# main.net
KiCad netlist of a schematic drawn in Altium Designer
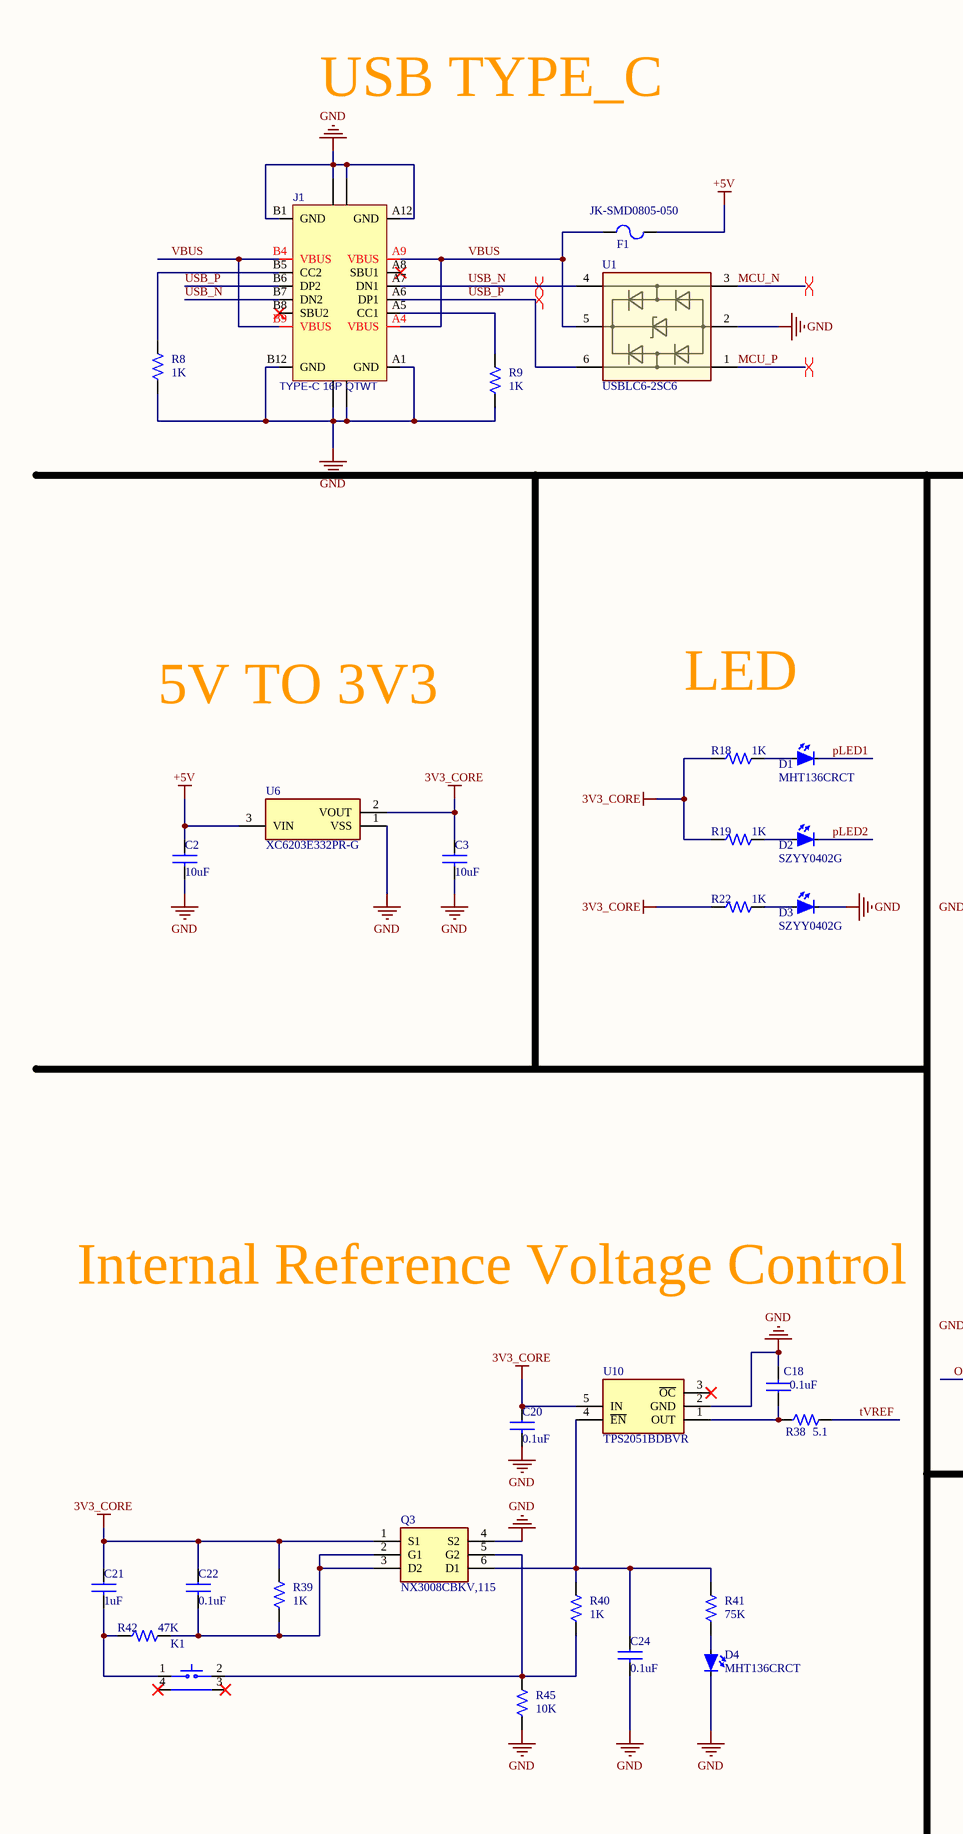
[diagram p0: main.SchDoc, left]
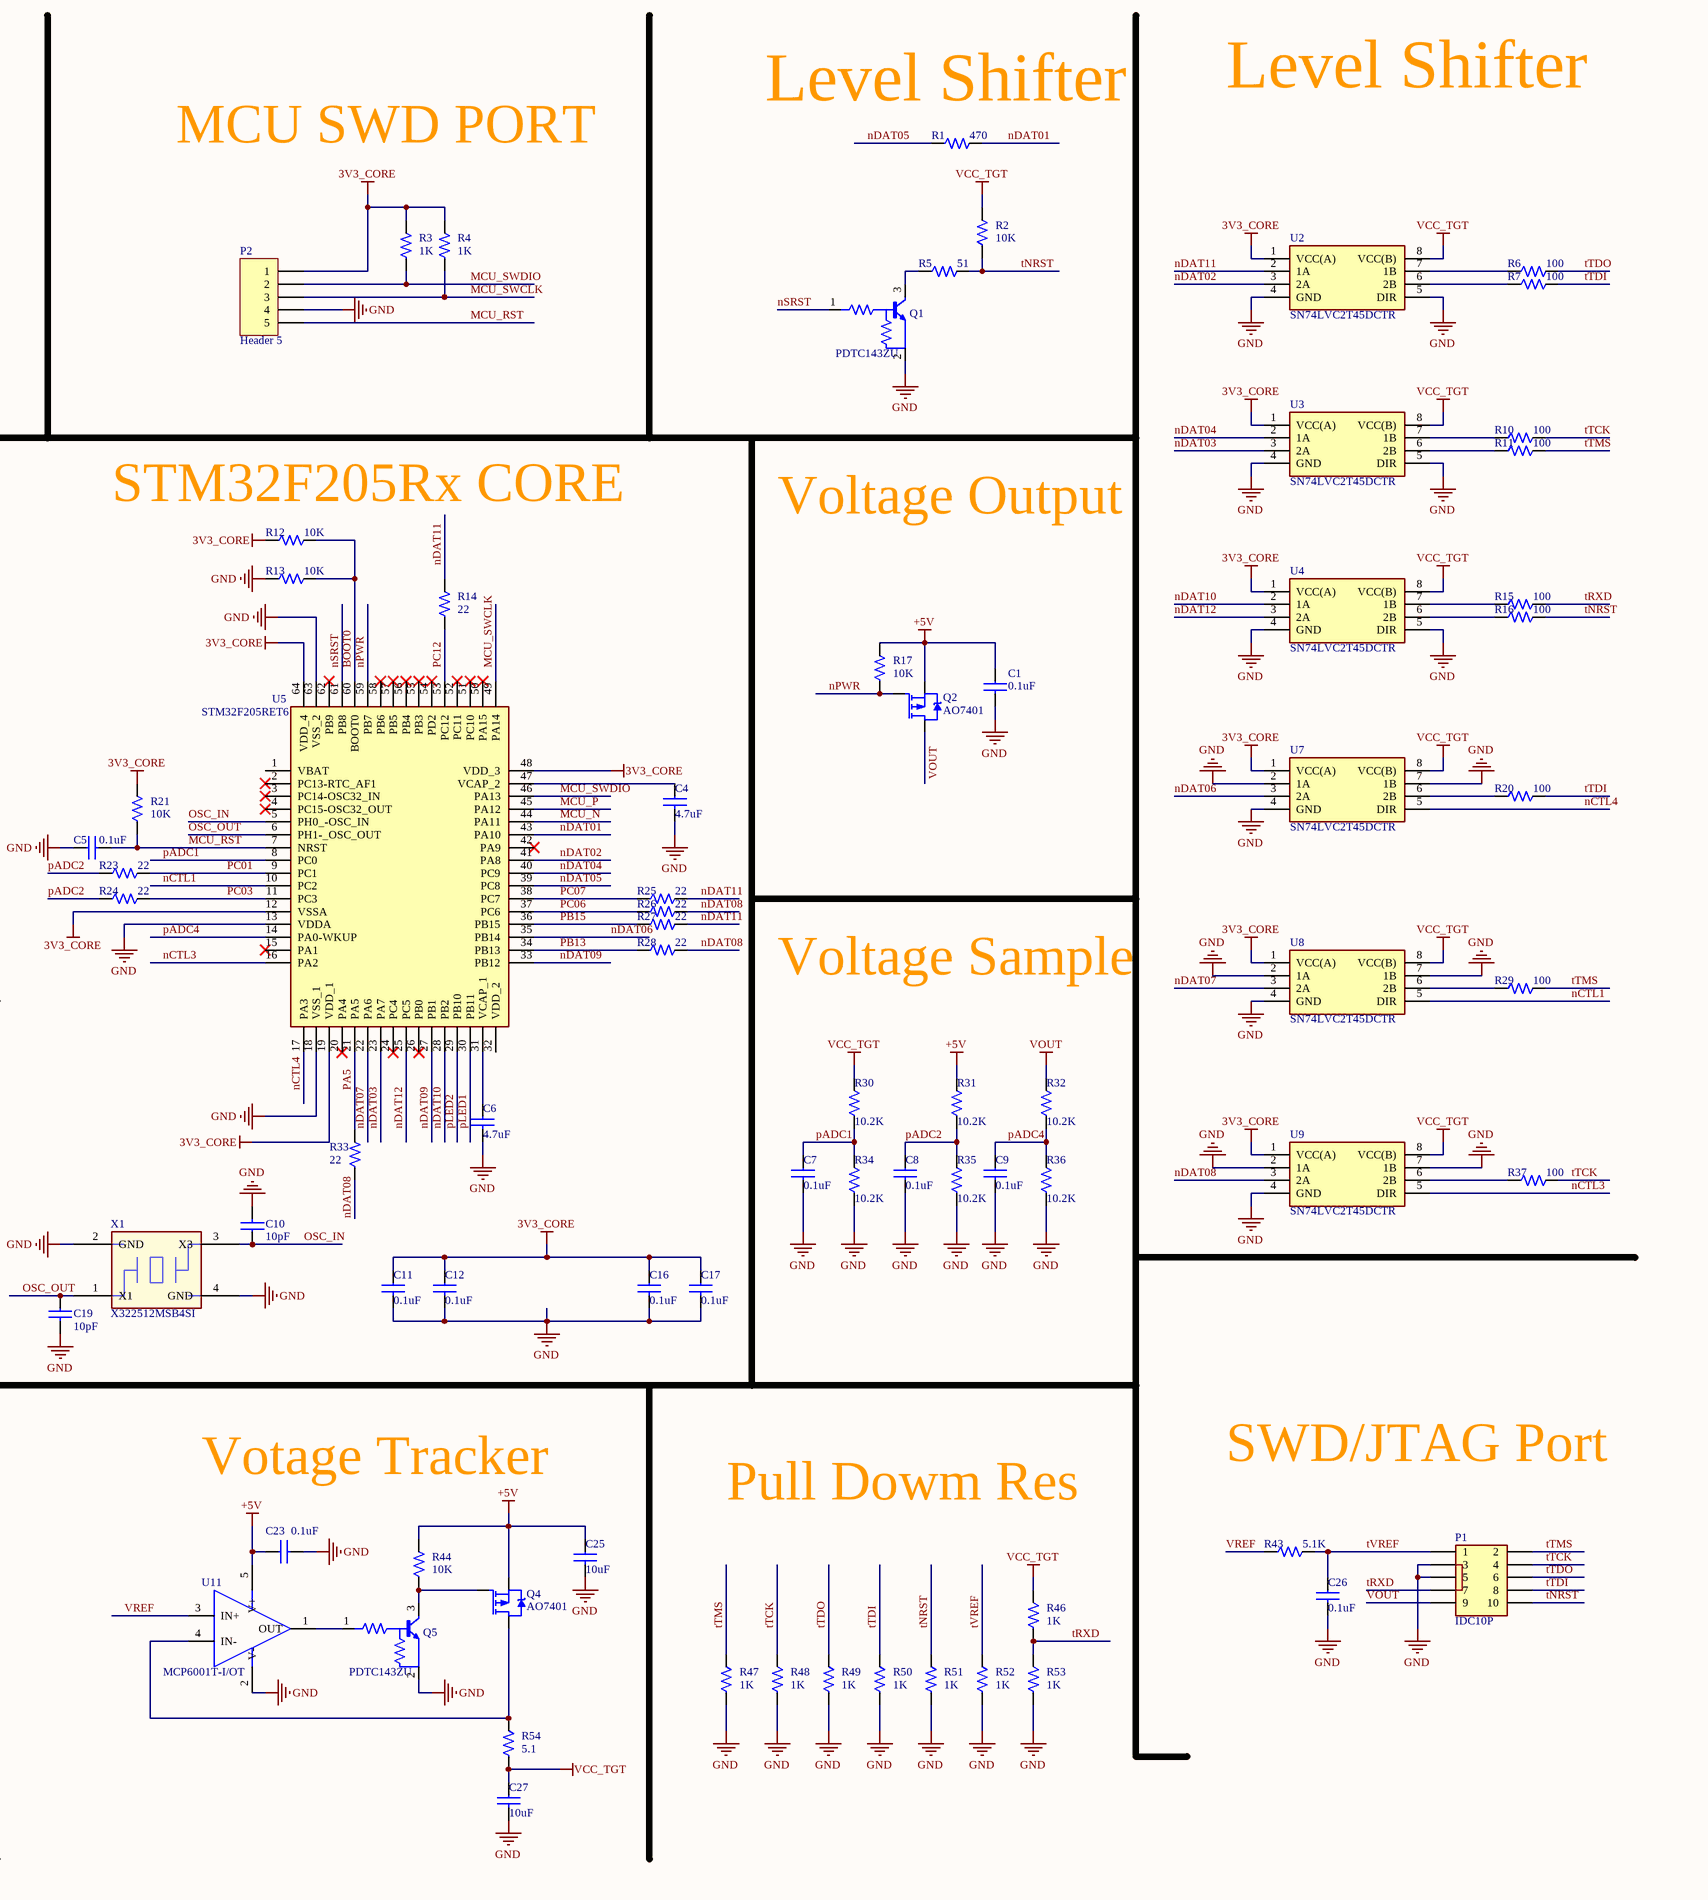
[diagram p1: main.SchDoc, right]

(export (version "E")
  (design (tool "Eeschema 10.0.6"))
  (components
    (comp (ref "C1")
      (value "0.1uF")
      (footprint "C0402")
      (description "CAP CER 0.1uF 25V X7R 0402")
      (fields (field (name "PART NUMBER") "E01C01711") (field (name "POWER") "25V"))
      (libsource (lib "Library") (part "CAP NON POL"))
    )
    (comp (ref "C2")
      (value "10uF")
      (footprint "C0402")
      (description "CAP CER 10uF 6.3V X5R 0402")
      (fields (field (name "PART NUMBER") "E01C02000") (field (name "POWER") "6.3V"))
      (libsource (lib "Library") (part "CAP NON POL"))
    )
    (comp (ref "C3")
      (value "10uF")
      (footprint "C0402")
      (description "CAP CER 10uF 6.3V X5R 0402")
      (fields (field (name "PART NUMBER") "E01C02000") (field (name "POWER") "6.3V"))
      (libsource (lib "Library") (part "CAP NON POL"))
    )
    (comp (ref "C4")
      (value "4.7uF")
      (footprint "C0402")
      (description "CAP CER 4.7uF 10V X5R 0402")
      (fields (field (name "PART NUMBER") "E01C01942") (field (name "POWER") "10V"))
      (libsource (lib "Library") (part "CAP NON POL"))
    )
    (comp (ref "C5")
      (value "0.1uF")
      (footprint "C0402")
      (description "CAP CER 0.1uF 25V X7R 0402")
      (fields (field (name "PART NUMBER") "E01C01711") (field (name "POWER") "25V"))
      (libsource (lib "Library") (part "CAP NON POL"))
    )
    (comp (ref "C6")
      (value "4.7uF")
      (footprint "C0402")
      (description "CAP CER 4.7uF 10V X5R 0402")
      (fields (field (name "PART NUMBER") "E01C01942") (field (name "POWER") "10V"))
      (libsource (lib "Library") (part "CAP NON POL"))
    )
    (comp (ref "C7")
      (value "0.1uF")
      (footprint "C0402")
      (description "CAP CER 0.1uF 16V X7R 0402")
      (fields (field (name "PART NUMBER") "E01C01713") (field (name "POWER") "16V"))
      (libsource (lib "Library") (part "CAP NON POL"))
    )
    (comp (ref "C8")
      (value "0.1uF")
      (footprint "C0402")
      (description "CAP CER 0.1uF 16V X7R 0402")
      (fields (field (name "PART NUMBER") "E01C01713") (field (name "POWER") "16V"))
      (libsource (lib "Library") (part "CAP NON POL"))
    )
    (comp (ref "C9")
      (value "0.1uF")
      (footprint "C0402")
      (description "CAP CER 0.1uF 16V X7R 0402")
      (fields (field (name "PART NUMBER") "E01C01713") (field (name "POWER") "16V"))
      (libsource (lib "Library") (part "CAP NON POL"))
    )
    (comp (ref "C10")
      (value "10pF")
      (footprint "C0402")
      (description "CAP CER 10pF 50V C0G/NP0 0402")
      (fields (field (name "PART NUMBER") "E01C00842") (field (name "POWER") "50V"))
      (libsource (lib "Library") (part "CAP NON POL"))
    )
    (comp (ref "C11")
      (value "0.1uF")
      (footprint "C0402")
      (description "CAP CER 0.1uF 16V X7R 0402")
      (fields (field (name "PART NUMBER") "E01C01713") (field (name "POWER") "16V"))
      (libsource (lib "Library") (part "CAP NON POL"))
    )
    (comp (ref "C12")
      (value "0.1uF")
      (footprint "C0402")
      (description "CAP CER 0.1uF 16V X7R 0402")
      (fields (field (name "PART NUMBER") "E01C01713") (field (name "POWER") "16V"))
      (libsource (lib "Library") (part "CAP NON POL"))
    )
    (comp (ref "C16")
      (value "0.1uF")
      (footprint "C0402")
      (description "CAP CER 0.1uF 16V X7R 0402")
      (fields (field (name "PART NUMBER") "E01C01713") (field (name "POWER") "16V"))
      (libsource (lib "Library") (part "CAP NON POL"))
    )
    (comp (ref "C17")
      (value "0.1uF")
      (footprint "C0402")
      (description "CAP CER 0.1uF 16V X7R 0402")
      (fields (field (name "PART NUMBER") "E01C01713") (field (name "POWER") "16V"))
      (libsource (lib "Library") (part "CAP NON POL"))
    )
    (comp (ref "C18")
      (value "0.1uF")
      (footprint "C0402")
      (description "CAP CER 0.1uF 25V X7R 0402")
      (fields (field (name "PART NUMBER") "E01C01711") (field (name "POWER") "25V"))
      (libsource (lib "Library") (part "CAP NON POL"))
    )
    (comp (ref "C19")
      (value "10pF")
      (footprint "C0402")
      (description "CAP CER 10pF 50V C0G/NP0 0402")
      (fields (field (name "PART NUMBER") "E01C00842") (field (name "POWER") "50V"))
      (libsource (lib "Library") (part "CAP NON POL"))
    )
    (comp (ref "C20")
      (value "0.1uF")
      (footprint "C0402")
      (description "CAP CER 0.1uF 25V X7R 0402")
      (fields (field (name "PART NUMBER") "E01C01711") (field (name "POWER") "25V"))
      (libsource (lib "Library") (part "CAP NON POL"))
    )
    (comp (ref "C21")
      (value "1uF")
      (footprint "C0402")
      (description "CAP CER 1uF 6.3V X5R 0402")
      (fields (field (name "PART NUMBER") "E01C01812") (field (name "POWER") "6.3V"))
      (libsource (lib "Library") (part "CAP NON POL"))
    )
    (comp (ref "C22")
      (value "0.1uF")
      (footprint "C0402")
      (description "CAP CER 0.1uF 25V X7R 0402")
      (fields (field (name "PART NUMBER") "E01C01711") (field (name "POWER") "25V"))
      (libsource (lib "Library") (part "CAP NON POL"))
    )
    (comp (ref "C23")
      (value "0.1uF")
      (footprint "C0402")
      (description "CAP CER 0.1uF 16V X7R 0402")
      (fields (field (name "PART NUMBER") "E01C01713") (field (name "POWER") "16V"))
      (libsource (lib "Library") (part "CAP NON POL"))
    )
    (comp (ref "C24")
      (value "0.1uF")
      (footprint "C0402")
      (description "CAP CER 0.1uF 25V X7R 0402")
      (fields (field (name "PART NUMBER") "E01C01711") (field (name "POWER") "25V"))
      (libsource (lib "Library") (part "CAP NON POL"))
    )
    (comp (ref "C25")
      (value "10uF")
      (footprint "C0402")
      (description "CAP CER 10uF 6.3V X5R 0402")
      (fields (field (name "PART NUMBER") "E01C02000") (field (name "POWER") "6.3V"))
      (libsource (lib "Library") (part "CAP NON POL"))
    )
    (comp (ref "C26")
      (value "0.1uF")
      (footprint "C0402")
      (description "CAP CER 0.1uF 25V X7R 0402")
      (fields (field (name "PART NUMBER") "E01C01711") (field (name "POWER") "25V"))
      (libsource (lib "Library") (part "CAP NON POL"))
    )
    (comp (ref "C27")
      (value "10uF")
      (footprint "C0603")
      (description "CAP CER 10uF 16V X5R 0603")
      (fields (field (name "PART NUMBER") "E01C01977") (field (name "POWER") "16V"))
      (libsource (lib "Library") (part "CAP NON POL"))
    )
    (comp (ref "D1")
      (value "MHT136CRCT")
      (footprint "LED-0402")
      (description "SMD,发光颜色:红色;功率:60mW;正向电流:5mA;主波长:617.5nm~633.5nm;")
      (fields (field (name "PART NUMBER") "E01D00051") (field (name "MFG") "MEIHUA"))
      (libsource (lib "Library") (part "LED"))
    )
    (comp (ref "D2")
      (value "SZYY0402G")
      (footprint "LED-0402")
      (description "SMD,发光颜色:翠绿色;")
      (fields (field (name "PART NUMBER") "E01D00010") (field (name "MFG") "YONGYU"))
      (libsource (lib "Library") (part "LED"))
    )
    (comp (ref "D3")
      (value "SZYY0402G")
      (footprint "LED-0402")
      (description "SMD,发光颜色:翠绿色;")
      (fields (field (name "PART NUMBER") "E01D00010") (field (name "MFG") "YONGYU"))
      (libsource (lib "Library") (part "LED"))
    )
    (comp (ref "D4")
      (value "MHT136CRCT")
      (footprint "LED-0402")
      (description "SMD,发光颜色:红色;功率:60mW;正向电流:5mA;主波长:617.5nm~633.5nm;")
      (fields (field (name "PART NUMBER") "E01D00051") (field (name "MFG") "MEIHUA"))
      (libsource (lib "Library") (part "LED"))
    )
    (comp (ref "F1")
      (value "JK-SMD0805-050")
      (footprint "FUSE_0805")
      (description "0805 0.5A 6V PTC FUSE")
      (fields (field (name "PART NUMBER") "E01F00003") (field (name "POWER") "6V"))
      (libsource (lib "Library") (part "FUSE"))
    )
    (comp (ref "J1")
      (value "TYPE-C 16P QTWT")
      (footprint "USB-C-16-SM")
      (description "SMD,Type_C母座；16P；卧贴;")
      (fields (field (name "PART NUMBER") "E04C00183") (field (name "MFG") "SHOU HAN"))
      (libsource (lib "Library") (part "USB2.0_Type-C_16Pin"))
    )
    (comp (ref "K1")
      (value "TS36CA-0.6")
      (footprint "SW4-3X6X3R5-WS")
      (description "SMD,轻触开关 3*6*3.5侧按 直径0.6定位柱 白体黑头")
      (fields (field (name "PART NUMBER") "E01S00008") (field (name "MFG") "SHOU HAN(首韩)"))
      (libsource (lib "Library") (part "SW-4Pin_1"))
    )
    (comp (ref "P1")
      (value "IDC10P")
      (footprint "IDC10P-2R54-WS")
      (description "SMD.2.54mm简牛座;卧贴;排数:2;每排PIN数:5")
      (fields (field (name "PART NUMBER") "E04C00186") (field (name "MFG") "/"))
      (libsource (lib "Library") (part "CON2x5"))
    )
    (comp (ref "P2")
      (value "Device Name")
      (footprint "HDR-1.27-1X5")
      (description "5脚排针")
      (fields (field (name "SCH NAME") "Header 5") (field (name "PART NUMBER") "E04C00187"))
      (libsource (lib "Library") (part "Header 5"))
    )
    (comp (ref "Q1")
      (value "PDTC143ZU")
      (footprint "SOT323")
      (fields (field (name "PART NUMBER") "E01T00045") (field (name "MFG") "Nexperia"))
      (libsource (lib "Library") (part "Transistor Digital NPN"))
    )
    (comp (ref "Q2")
      (value "AO7401")
      (footprint "SOT23-3")
      (fields (field (name "PART NUMBER") "E01T00044") (field (name "MFG") "AOS"))
      (libsource (lib "Library") (part "PMOS"))
    )
    (comp (ref "Q3")
      (value "NX3008CBKV,115")
      (footprint "SOT666")
      (fields (field (name "PART NUMBER") "E01T00046") (field (name "MFG") "Nexperia"))
      (libsource (lib "Library") (part "PMOS_NMOS_6"))
    )
    (comp (ref "Q4")
      (value "AO7401")
      (footprint "SOT23-3")
      (fields (field (name "PART NUMBER") "E01T00044") (field (name "MFG") "AOS"))
      (libsource (lib "Library") (part "PMOS"))
    )
    (comp (ref "Q5")
      (value "PDTC143ZU")
      (footprint "SOT323")
      (fields (field (name "PART NUMBER") "E01T00045") (field (name "MFG") "Nexperia"))
      (libsource (lib "Library") (part "Transistor Digital NPN"))
    )
    (comp (ref "R1")
      (value "470")
      (footprint "R0402")
      (description "RES SMD 470 OHM 5% 1/16W 0402")
      (fields (field (name "PART NUMBER") "E01R01244") (field (name "POWER") "0.063W，1/16W"))
      (libsource (lib "Library") (part "RES"))
    )
    (comp (ref "R2")
      (value "10K")
      (footprint "R0402")
      (description "RES SMD 10K OHM 1% 1/16W 0402")
      (fields (field (name "PART NUMBER") "E01R01984") (field (name "POWER") "0.063W，1/16W"))
      (libsource (lib "Library") (part "RES"))
    )
    (comp (ref "R3")
      (value "1K")
      (footprint "R0402")
      (description "RES SMD 1K OHM 1% 1/16W 0402")
      (fields (field (name "PART NUMBER") "E01R01430") (field (name "POWER") "0.063W，1/16W"))
      (libsource (lib "Library") (part "RES"))
    )
    (comp (ref "R4")
      (value "1K")
      (footprint "R0402")
      (description "RES SMD 1K OHM 1% 1/16W 0402")
      (fields (field (name "PART NUMBER") "E01R01430") (field (name "POWER") "0.063W，1/16W"))
      (libsource (lib "Library") (part "RES"))
    )
    (comp (ref "R5")
      (value "51")
      (footprint "R0402")
      (description "RES SMD 51 OHM 1% 1/16W 0402")
      (fields (field (name "PART NUMBER") "E01R00720") (field (name "POWER") "0.063W，1/16W"))
      (libsource (lib "Library") (part "RES"))
    )
    (comp (ref "R6")
      (value "100")
      (footprint "R0402")
      (description "RES SMD 100 OHM 5% 1/16W 0402")
      (fields (field (name "PART NUMBER") "E01R00875") (field (name "POWER") "0.063W，1/16W"))
      (libsource (lib "Library") (part "RES"))
    )
    (comp (ref "R7")
      (value "100")
      (footprint "R0402")
      (description "RES SMD 100 OHM 5% 1/16W 0402")
      (fields (field (name "PART NUMBER") "E01R00875") (field (name "POWER") "0.063W，1/16W"))
      (libsource (lib "Library") (part "RES"))
    )
    (comp (ref "R8")
      (value "1K")
      (footprint "R0402")
      (description "RES SMD 1K OHM 1% 1/16W 0402")
      (fields (field (name "PART NUMBER") "E01R01430") (field (name "POWER") "0.063W，1/16W"))
      (libsource (lib "Library") (part "RES"))
    )
    (comp (ref "R9")
      (value "1K")
      (footprint "R0402")
      (description "RES SMD 1K OHM 1% 1/16W 0402")
      (fields (field (name "PART NUMBER") "E01R01430") (field (name "POWER") "0.063W，1/16W"))
      (libsource (lib "Library") (part "RES"))
    )
    (comp (ref "R10")
      (value "100")
      (footprint "R0402")
      (description "RES SMD 100 OHM 5% 1/16W 0402")
      (fields (field (name "PART NUMBER") "E01R00875") (field (name "POWER") "0.063W，1/16W"))
      (libsource (lib "Library") (part "RES"))
    )
    (comp (ref "R11")
      (value "100")
      (footprint "R0402")
      (description "RES SMD 100 OHM 5% 1/16W 0402")
      (fields (field (name "PART NUMBER") "E01R00875") (field (name "POWER") "0.063W，1/16W"))
      (libsource (lib "Library") (part "RES"))
    )
    (comp (ref "R12")
      (value "10K")
      (footprint "R0402")
      (description "RES SMD 10K OHM 1% 1/16W 0402")
      (fields (field (name "PART NUMBER") "E01R01984") (field (name "POWER") "0.063W，1/16W"))
      (libsource (lib "Library") (part "RES"))
    )
    (comp (ref "R13")
      (value "10K")
      (footprint "R0402")
      (description "RES SMD 10K OHM 1% 1/16W 0402")
      (fields (field (name "PART NUMBER") "E01R01984") (field (name "POWER") "0.063W，1/16W"))
      (libsource (lib "Library") (part "RES"))
    )
    (comp (ref "R14")
      (value "22")
      (footprint "R0402")
      (description "RES SMD 22 OHM 1% 1/16W 0402")
      (fields (field (name "PART NUMBER") "E01R00510") (field (name "POWER") "0.063W，1/16W"))
      (libsource (lib "Library") (part "RES"))
    )
    (comp (ref "R15")
      (value "100")
      (footprint "R0402")
      (description "RES SMD 100 OHM 5% 1/16W 0402")
      (fields (field (name "PART NUMBER") "E01R00875") (field (name "POWER") "0.063W，1/16W"))
      (libsource (lib "Library") (part "RES"))
    )
    (comp (ref "R16")
      (value "100")
      (footprint "R0402")
      (description "RES SMD 100 OHM 5% 1/16W 0402")
      (fields (field (name "PART NUMBER") "E01R00875") (field (name "POWER") "0.063W，1/16W"))
      (libsource (lib "Library") (part "RES"))
    )
    (comp (ref "R17")
      (value "10K")
      (footprint "R0402")
      (description "RES SMD 10K OHM 1% 1/16W 0402")
      (fields (field (name "PART NUMBER") "E01R01984") (field (name "POWER") "0.063W，1/16W"))
      (libsource (lib "Library") (part "RES"))
    )
    (comp (ref "R18")
      (value "1K")
      (footprint "R0402")
      (description "RES SMD 1K OHM 1% 1/16W 0402")
      (fields (field (name "PART NUMBER") "E01R01430") (field (name "POWER") "0.063W，1/16W"))
      (libsource (lib "Library") (part "RES"))
    )
    (comp (ref "R19")
      (value "1K")
      (footprint "R0402")
      (description "RES SMD 1K OHM 1% 1/16W 0402")
      (fields (field (name "PART NUMBER") "E01R01430") (field (name "POWER") "0.063W，1/16W"))
      (libsource (lib "Library") (part "RES"))
    )
    (comp (ref "R20")
      (value "100")
      (footprint "R0402")
      (description "RES SMD 100 OHM 5% 1/16W 0402")
      (fields (field (name "PART NUMBER") "E01R00875") (field (name "POWER") "0.063W，1/16W"))
      (libsource (lib "Library") (part "RES"))
    )
    (comp (ref "R21")
      (value "10K")
      (footprint "R0402")
      (description "RES SMD 10K OHM 1% 1/16W 0402")
      (fields (field (name "PART NUMBER") "E01R01984") (field (name "POWER") "0.063W，1/16W"))
      (libsource (lib "Library") (part "RES"))
    )
    (comp (ref "R22")
      (value "1K")
      (footprint "R0402")
      (description "RES SMD 1K OHM 1% 1/16W 0402")
      (fields (field (name "PART NUMBER") "E01R01430") (field (name "POWER") "0.063W，1/16W"))
      (libsource (lib "Library") (part "RES"))
    )
    (comp (ref "R23")
      (value "22")
      (footprint "R0402")
      (description "RES SMD 22 OHM 1% 1/16W 0402")
      (fields (field (name "PART NUMBER") "E01R00510") (field (name "POWER") "0.063W，1/16W"))
      (libsource (lib "Library") (part "RES"))
    )
    (comp (ref "R24")
      (value "22")
      (footprint "R0402")
      (description "RES SMD 22 OHM 1% 1/16W 0402")
      (fields (field (name "PART NUMBER") "E01R00510") (field (name "POWER") "0.063W，1/16W"))
      (libsource (lib "Library") (part "RES"))
    )
    (comp (ref "R25")
      (value "22")
      (footprint "R0402")
      (description "RES SMD 22 OHM 1% 1/16W 0402")
      (fields (field (name "PART NUMBER") "E01R00510") (field (name "POWER") "0.063W，1/16W"))
      (libsource (lib "Library") (part "RES"))
    )
    (comp (ref "R26")
      (value "22")
      (footprint "R0402")
      (description "RES SMD 22 OHM 1% 1/16W 0402")
      (fields (field (name "PART NUMBER") "E01R00510") (field (name "POWER") "0.063W，1/16W"))
      (libsource (lib "Library") (part "RES"))
    )
    (comp (ref "R27")
      (value "22")
      (footprint "R0402")
      (description "RES SMD 22 OHM 1% 1/16W 0402")
      (fields (field (name "PART NUMBER") "E01R00510") (field (name "POWER") "0.063W，1/16W"))
      (libsource (lib "Library") (part "RES"))
    )
    (comp (ref "R28")
      (value "22")
      (footprint "R0402")
      (description "RES SMD 22 OHM 1% 1/16W 0402")
      (fields (field (name "PART NUMBER") "E01R00510") (field (name "POWER") "0.063W，1/16W"))
      (libsource (lib "Library") (part "RES"))
    )
    (comp (ref "R29")
      (value "100")
      (footprint "R0402")
      (description "RES SMD 100 OHM 5% 1/16W 0402")
      (fields (field (name "PART NUMBER") "E01R00875") (field (name "POWER") "0.063W，1/16W"))
      (libsource (lib "Library") (part "RES"))
    )
    (comp (ref "R30")
      (value "10.2K")
      (footprint "R0402")
      (description "RES SMD 10.2K OHM 1% 1/16W 0402")
      (fields (field (name "PART NUMBER") "E01R01988") (field (name "POWER") "0.063W，1/16W"))
      (libsource (lib "Library") (part "RES"))
    )
    (comp (ref "R31")
      (value "10.2K")
      (footprint "R0402")
      (description "RES SMD 10.2K OHM 1% 1/16W 0402")
      (fields (field (name "PART NUMBER") "E01R01988") (field (name "POWER") "0.063W，1/16W"))
      (libsource (lib "Library") (part "RES"))
    )
    (comp (ref "R32")
      (value "10.2K")
      (footprint "R0402")
      (description "RES SMD 10.2K OHM 1% 1/16W 0402")
      (fields (field (name "PART NUMBER") "E01R01988") (field (name "POWER") "0.063W，1/16W"))
      (libsource (lib "Library") (part "RES"))
    )
    (comp (ref "R33")
      (value "22")
      (footprint "R0402")
      (description "RES SMD 22 OHM 1% 1/16W 0402")
      (fields (field (name "PART NUMBER") "E01R00510") (field (name "POWER") "0.063W，1/16W"))
      (libsource (lib "Library") (part "RES"))
    )
    (comp (ref "R34")
      (value "10.2K")
      (footprint "R0402")
      (description "RES SMD 10.2K OHM 1% 1/16W 0402")
      (fields (field (name "PART NUMBER") "E01R01988") (field (name "POWER") "0.063W，1/16W"))
      (libsource (lib "Library") (part "RES"))
    )
    (comp (ref "R35")
      (value "10.2K")
      (footprint "R0402")
      (description "RES SMD 10.2K OHM 1% 1/16W 0402")
      (fields (field (name "PART NUMBER") "E01R01988") (field (name "POWER") "0.063W，1/16W"))
      (libsource (lib "Library") (part "RES"))
    )
    (comp (ref "R36")
      (value "10.2K")
      (footprint "R0402")
      (description "RES SMD 10.2K OHM 1% 1/16W 0402")
      (fields (field (name "PART NUMBER") "E01R01988") (field (name "POWER") "0.063W，1/16W"))
      (libsource (lib "Library") (part "RES"))
    )
    (comp (ref "R37")
      (value "100")
      (footprint "R0402")
      (description "RES SMD 100 OHM 5% 1/16W 0402")
      (fields (field (name "PART NUMBER") "E01R00875") (field (name "POWER") "0.063W，1/16W"))
      (libsource (lib "Library") (part "RES"))
    )
    (comp (ref "R38")
      (value "5.1")
      (footprint "R0402")
      (description "RES SMD 5.1 OHM 1% 1/16W 0402")
      (fields (field (name "PART NUMBER") "E01R00242") (field (name "POWER") "0.063W，1/16W"))
      (libsource (lib "Library") (part "RES"))
    )
    (comp (ref "R39")
      (value "1K")
      (footprint "R0402")
      (description "RES SMD 1K OHM 1% 1/16W 0402")
      (fields (field (name "PART NUMBER") "E01R01430") (field (name "POWER") "0.063W，1/16W"))
      (libsource (lib "Library") (part "RES"))
    )
    (comp (ref "R40")
      (value "1K")
      (footprint "R0402")
      (description "RES SMD 1K OHM 1% 1/16W 0402")
      (fields (field (name "PART NUMBER") "E01R01430") (field (name "POWER") "0.063W，1/16W"))
      (libsource (lib "Library") (part "RES"))
    )
    (comp (ref "R41")
      (value "75K")
      (footprint "R0402")
      (description "RES SMD 75K OHM 1% 1/16W 0402")
      (fields (field (name "PART NUMBER") "E01R02470") (field (name "POWER") "0.063W，1/16W"))
      (libsource (lib "Library") (part "RES"))
    )
    (comp (ref "R42")
      (value "47K")
      (footprint "R0402")
      (description "RES SMD 47K OHM 1% 1/16W 0402")
      (fields (field (name "PART NUMBER") "E01R02353") (field (name "POWER") "0.063W，1/16W"))
      (libsource (lib "Library") (part "RES"))
    )
    (comp (ref "R43")
      (value "5.1K")
      (footprint "R0402")
      (description "RES SMD 5.1K OHM 1% 1/16W 0402")
      (fields (field (name "PART NUMBER") "E01R01818") (field (name "POWER") "0.063W，1/16W"))
      (libsource (lib "Library") (part "RES"))
    )
    (comp (ref "R44")
      (value "10K")
      (footprint "R0402")
      (description "RES SMD 10K OHM 1% 1/16W 0402")
      (fields (field (name "PART NUMBER") "E01R01984") (field (name "POWER") "0.063W，1/16W"))
      (libsource (lib "Library") (part "RES"))
    )
    (comp (ref "R45")
      (value "10K")
      (footprint "R0402")
      (description "RES SMD 10K OHM 1% 1/16W 0402")
      (fields (field (name "PART NUMBER") "E01R01984") (field (name "POWER") "0.063W，1/16W"))
      (libsource (lib "Library") (part "RES"))
    )
    (comp (ref "R46")
      (value "1K")
      (footprint "R0402")
      (description "RES SMD 1K OHM 1% 1/16W 0402")
      (fields (field (name "PART NUMBER") "E01R01430") (field (name "POWER") "0.063W，1/16W"))
      (libsource (lib "Library") (part "RES"))
    )
    (comp (ref "R47")
      (value "1K")
      (footprint "R0402")
      (description "RES SMD 1K OHM 1% 1/16W 0402")
      (fields (field (name "PART NUMBER") "E01R01430") (field (name "POWER") "0.063W，1/16W"))
      (libsource (lib "Library") (part "RES"))
    )
    (comp (ref "R48")
      (value "1K")
      (footprint "R0402")
      (description "RES SMD 1K OHM 1% 1/16W 0402")
      (fields (field (name "PART NUMBER") "E01R01430") (field (name "POWER") "0.063W，1/16W"))
      (libsource (lib "Library") (part "RES"))
    )
    (comp (ref "R49")
      (value "1K")
      (footprint "R0402")
      (description "RES SMD 1K OHM 1% 1/16W 0402")
      (fields (field (name "PART NUMBER") "E01R01430") (field (name "POWER") "0.063W，1/16W"))
      (libsource (lib "Library") (part "RES"))
    )
    (comp (ref "R50")
      (value "1K")
      (footprint "R0402")
      (description "RES SMD 1K OHM 1% 1/16W 0402")
      (fields (field (name "PART NUMBER") "E01R01430") (field (name "POWER") "0.063W，1/16W"))
      (libsource (lib "Library") (part "RES"))
    )
    (comp (ref "R51")
      (value "1K")
      (footprint "R0402")
      (description "RES SMD 1K OHM 1% 1/16W 0402")
      (fields (field (name "PART NUMBER") "E01R01430") (field (name "POWER") "0.063W，1/16W"))
      (libsource (lib "Library") (part "RES"))
    )
    (comp (ref "R52")
      (value "1K")
      (footprint "R0402")
      (description "RES SMD 1K OHM 1% 1/16W 0402")
      (fields (field (name "PART NUMBER") "E01R01430") (field (name "POWER") "0.063W，1/16W"))
      (libsource (lib "Library") (part "RES"))
    )
    (comp (ref "R53")
      (value "1K")
      (footprint "R0402")
      (description "RES SMD 1K OHM 1% 1/16W 0402")
      (fields (field (name "PART NUMBER") "E01R01430") (field (name "POWER") "0.063W，1/16W"))
      (libsource (lib "Library") (part "RES"))
    )
    (comp (ref "R54")
      (value "5.1")
      (footprint "R0402")
      (description "RES SMD 5.1 OHM 1% 1/16W 0402")
      (fields (field (name "PART NUMBER") "E01R00242") (field (name "POWER") "0.063W，1/16W"))
      (libsource (lib "Library") (part "RES"))
    )
    (comp (ref "U1")
      (value "USBLC6-2SC6")
      (footprint "SOT23-6")
      (description "SMD,USB 2.0高速接口的ESD保护;极性:单向;反向截止电压(Vrwm):5.25V;最大钳位电压:17V;峰值脉冲电流(Ipp)@10/1000us:5A;击穿电压:6V;")
      (fields (field (name "PART NUMBER") "E02P00418") (field (name "MFG") "ST"))
      (libsource (lib "Library") (part "USBLC6-2SC6"))
    )
    (comp (ref "U2")
      (value "SN74LVC2T45DCTR")
      (footprint "SSOP8")
      (description "SMD,数据速率:420Mbps;电压(VCCA):1.2V~5.5V;电压(VCCB):1.2V~5.5V;通道数:2;")
      (fields (field (name "PART NUMBER") "E02P00290") (field (name "MFG") "TI"))
      (libsource (lib "Library") (part "74LVC2T45"))
    )
    (comp (ref "U3")
      (value "SN74LVC2T45DCTR")
      (footprint "SSOP8")
      (description "SMD,数据速率:420Mbps;电压(VCCA):1.2V~5.5V;电压(VCCB):1.2V~5.5V;通道数:2;")
      (fields (field (name "PART NUMBER") "E02P00290") (field (name "MFG") "TI"))
      (libsource (lib "Library") (part "74LVC2T45"))
    )
    (comp (ref "U4")
      (value "SN74LVC2T45DCTR")
      (footprint "SSOP8")
      (description "SMD,数据速率:420Mbps;电压(VCCA):1.2V~5.5V;电压(VCCB):1.2V~5.5V;通道数:2;")
      (fields (field (name "PART NUMBER") "E02P00290") (field (name "MFG") "TI"))
      (libsource (lib "Library") (part "74LVC2T45"))
    )
    (comp (ref "U5")
      (value "STM32F205RET6")
      (footprint "LQFP64-0R5-10X10")
      (description "SMD,CPU内核:CM3;程序存储容量:512KB;RAM:128KB;GPIO端口数量:51;")
      (fields (field (name "PART NUMBER") "E02P00420") (field (name "POWER") "1.8V~3.6V"))
      (libsource (lib "Library") (part "STM32F205RxT6"))
    )
    (comp (ref "U6")
      (value "XC6203E332PR-G")
      (footprint "SOT89")
      (description "SMD,输出类型:固定;最大输入电压:8V;输出电压:3.3V;最大输出电流:400mA;电源纹波抑制比(PSRR):-;输出极性:正极;")
      (fields (field (name "PART NUMBER") "E02P00421") (field (name "POWER") "8.0V MAX"))
      (libsource (lib "Library") (part "XC6206"))
    )
    (comp (ref "U7")
      (value "SN74LVC2T45DCTR")
      (footprint "SSOP8")
      (description "SMD,数据速率:420Mbps;电压(VCCA):1.2V~5.5V;电压(VCCB):1.2V~5.5V;通道数:2;")
      (fields (field (name "PART NUMBER") "E02P00290") (field (name "MFG") "TI"))
      (libsource (lib "Library") (part "74LVC2T45"))
    )
    (comp (ref "U8")
      (value "SN74LVC2T45DCTR")
      (footprint "SSOP8")
      (description "SMD,数据速率:420Mbps;电压(VCCA):1.2V~5.5V;电压(VCCB):1.2V~5.5V;通道数:2;")
      (fields (field (name "PART NUMBER") "E02P00290") (field (name "MFG") "TI"))
      (libsource (lib "Library") (part "74LVC2T45"))
    )
    (comp (ref "U9")
      (value "SN74LVC2T45DCTR")
      (footprint "SSOP8")
      (description "SMD,数据速率:420Mbps;电压(VCCA):1.2V~5.5V;电压(VCCB):1.2V~5.5V;通道数:2;")
      (fields (field (name "PART NUMBER") "E02P00290") (field (name "MFG") "TI"))
      (libsource (lib "Library") (part "74LVC2T45"))
    )
    (comp (ref "U10")
      (value "TPS2051BDBVR")
      (footprint "SOT23-5")
      (description "SMD,高电平有效的 0.5A 负载、2.7-5.5V、70mΩ USB 电源开关。")
      (fields (field (name "PART NUMBER") "E02P00417") (field (name "POWER") "1V~5.5V"))
      (libsource (lib "Library") (part "TPS2051"))
    )
    (comp (ref "U11")
      (value "MCP6001T-I/OT")
      (footprint "SOT23-5")
      (description "SMD,低功耗单路运算放大器;支持共模输入电压范围为VDD+300mV至VSS-300mV的轨到轨输入和输出摆幅")
      (fields (field (name "PART NUMBER") "E02P00415") (field (name "POWER") "1.8V~6V"))
      (libsource (lib "Library") (part "MCP6001T"))
    )
    (comp (ref "X1")
      (value "X322512MSB4SI")
      (footprint "3225-4P")
      (description "SMD,频率:12MHz;常温频差:±10ppm;外接负载电容:20pF;频率稳定度(全温):±20ppm;")
      (fields (field (name "PART NUMBER") "E01X00040") (field (name "TOLERANCE") "±20ppm"))
      (libsource (lib "Library") (part "CRYSTAL 1-3_4Pin"))
    )
  )
  (nets
    (net (code "1") (name "+5V") (class "Default")
      (node (ref "C1") (pin "1") (pinfunction "1_1") (pintype "passive"))
      (node (ref "C2") (pin "1") (pinfunction "1_1") (pintype "passive"))
      (node (ref "C23") (pin "1") (pinfunction "1_1") (pintype "passive"))
      (node (ref "C25") (pin "1") (pinfunction "1_1") (pintype "passive"))
      (node (ref "F1") (pin "2") (pinfunction "2_2") (pintype "passive"))
      (node (ref "Q2") (pin "2") (pinfunction "S_2") (pintype "passive"))
      (node (ref "Q4") (pin "2") (pinfunction "S_2") (pintype "passive"))
      (node (ref "R17") (pin "2") (pinfunction "2_2") (pintype "passive"))
      (node (ref "R31") (pin "2") (pinfunction "2_2") (pintype "passive"))
      (node (ref "R44") (pin "2") (pinfunction "2_2") (pintype "passive"))
      (node (ref "U11") (pin "5") (pinfunction "V+_5") (pintype "passive"))
      (node (ref "U6") (pin "3") (pinfunction "VIN_3") (pintype "power_in"))
    )
    (net (code "2") (name "/BOOT0") (class "Default")
      (node (ref "R12") (pin "2") (pinfunction "2_2") (pintype "passive"))
      (node (ref "R13") (pin "2") (pinfunction "2_2") (pintype "passive"))
      (node (ref "U5") (pin "60") (pinfunction "BOOT0_60") (pintype "passive"))
    )
    (net (code "3") (name "/MCU_N") (class "Default")
      (node (ref "U1") (pin "3") (pinfunction "3_3") (pintype "passive"))
      (node (ref "U5") (pin "44") (pinfunction "PA11_44") (pintype "passive"))
    )
    (net (code "4") (name "/MCU_P") (class "Default")
      (node (ref "U1") (pin "1") (pinfunction "1_1") (pintype "passive"))
      (node (ref "U5") (pin "45") (pinfunction "PA12_45") (pintype "passive"))
    )
    (net (code "5") (name "/MCU_RST") (class "Default")
      (node (ref "C5") (pin "2") (pinfunction "2_2") (pintype "passive"))
      (node (ref "P2") (pin "5") (pinfunction "5_5") (pintype "passive"))
      (node (ref "R21") (pin "1") (pinfunction "1_1") (pintype "passive"))
      (node (ref "U5") (pin "7") (pinfunction "NRST_7") (pintype "passive"))
    )
    (net (code "6") (name "/MCU_SWCLK") (class "Default")
      (node (ref "P2") (pin "3") (pinfunction "3_3") (pintype "passive"))
      (node (ref "R4") (pin "1") (pinfunction "1_1") (pintype "passive"))
      (node (ref "U5") (pin "49") (pinfunction "PA14_49") (pintype "passive"))
    )
    (net (code "7") (name "/MCU_SWDIO") (class "Default")
      (node (ref "P2") (pin "2") (pinfunction "2_2") (pintype "passive"))
      (node (ref "R3") (pin "1") (pinfunction "1_1") (pintype "passive"))
      (node (ref "U5") (pin "46") (pinfunction "PA13_46") (pintype "passive"))
    )
    (net (code "8") (name "/OSC_IN") (class "Default")
      (node (ref "C10") (pin "1") (pinfunction "1_1") (pintype "passive"))
      (node (ref "U5") (pin "5") (pinfunction "PH0_-OSC_IN_5") (pintype "passive"))
      (node (ref "X1") (pin "3") (pinfunction "X3_3") (pintype "power_in"))
    )
    (net (code "9") (name "/OSC_OUT") (class "Default")
      (node (ref "C19") (pin "1") (pinfunction "1_1") (pintype "passive"))
      (node (ref "U5") (pin "6") (pinfunction "PH1-_OSC_OUT_6") (pintype "passive"))
      (node (ref "X1") (pin "1") (pinfunction "X1_1") (pintype "power_in"))
    )
    (net (code "10") (name "/PA5") (class "Default")
      (node (ref "R33") (pin "2") (pinfunction "2_2") (pintype "passive"))
      (node (ref "U5") (pin "21") (pinfunction "PA5_21") (pintype "passive"))
    )
    (net (code "11") (name "/PB13") (class "Default")
      (node (ref "R28") (pin "1") (pinfunction "1_1") (pintype "passive"))
      (node (ref "U5") (pin "34") (pinfunction "PB13_34") (pintype "passive"))
    )
    (net (code "12") (name "/PB15") (class "Default")
      (node (ref "R27") (pin "1") (pinfunction "1_1") (pintype "passive"))
      (node (ref "U5") (pin "36") (pinfunction "PB15_36") (pintype "passive"))
    )
    (net (code "13") (name "/PC01") (class "Default")
      (node (ref "R23") (pin "2") (pinfunction "2_2") (pintype "passive"))
      (node (ref "U5") (pin "9") (pinfunction "PC1_9") (pintype "passive"))
    )
    (net (code "14") (name "/PC03") (class "Default")
      (node (ref "R24") (pin "2") (pinfunction "2_2") (pintype "passive"))
      (node (ref "U5") (pin "11") (pinfunction "PC3_11") (pintype "passive"))
    )
    (net (code "15") (name "/PC06") (class "Default")
      (node (ref "R26") (pin "1") (pinfunction "1_1") (pintype "passive"))
      (node (ref "U5") (pin "37") (pinfunction "PC6_37") (pintype "passive"))
    )
    (net (code "16") (name "/PC07") (class "Default")
      (node (ref "R25") (pin "1") (pinfunction "1_1") (pintype "passive"))
      (node (ref "U5") (pin "38") (pinfunction "PC7_38") (pintype "passive"))
    )
    (net (code "17") (name "/PC12") (class "Default")
      (node (ref "R14") (pin "1") (pinfunction "1_1") (pintype "passive"))
      (node (ref "U5") (pin "53") (pinfunction "PC12_53") (pintype "passive"))
    )
    (net (code "18") (name "/USB_N") (class "Default")
      (node (ref "J1") (pin "A7") (pinfunction "DN1_A7") (pintype "passive"))
      (node (ref "J1") (pin "B7") (pinfunction "DN2_B7") (pintype "passive"))
      (node (ref "U1") (pin "4") (pinfunction "4_4") (pintype "passive"))
    )
    (net (code "19") (name "/USB_P") (class "Default")
      (node (ref "J1") (pin "A6") (pinfunction "DP1_A6") (pintype "passive"))
      (node (ref "J1") (pin "B6") (pinfunction "DP2_B6") (pintype "passive"))
      (node (ref "U1") (pin "6") (pinfunction "6_6") (pintype "passive"))
    )
    (net (code "20") (name "/VBUS") (class "Default")
      (node (ref "F1") (pin "1") (pinfunction "1_1") (pintype "passive"))
      (node (ref "J1") (pin "A4") (pinfunction "VBUS_A4") (pintype "passive"))
      (node (ref "J1") (pin "A9") (pinfunction "VBUS_A9") (pintype "passive"))
      (node (ref "J1") (pin "B4") (pinfunction "VBUS_B4") (pintype "passive"))
      (node (ref "J1") (pin "B9") (pinfunction "VBUS_B9") (pintype "passive"))
      (node (ref "U1") (pin "5") (pinfunction "5_5") (pintype "passive"))
    )
    (net (code "21") (name "/VREF") (class "Default")
      (node (ref "R43") (pin "1") (pinfunction "1_1") (pintype "passive"))
      (node (ref "U11") (pin "3") (pinfunction "IN+_3") (pintype "passive"))
    )
    (net (code "22") (name "/nCTL1") (class "Default")
      (node (ref "U5") (pin "10") (pinfunction "PC2_10") (pintype "passive"))
      (node (ref "U8") (pin "5") (pinfunction "DIR_5") (pintype "passive"))
    )
    (net (code "23") (name "/nCTL3") (class "Default")
      (node (ref "U5") (pin "16") (pinfunction "PA2_16") (pintype "passive"))
      (node (ref "U9") (pin "5") (pinfunction "DIR_5") (pintype "passive"))
    )
    (net (code "24") (name "/nCTL4") (class "Default")
      (node (ref "U5") (pin "17") (pinfunction "PA3_17") (pintype "passive"))
      (node (ref "U7") (pin "5") (pinfunction "DIR_5") (pintype "passive"))
    )
    (net (code "25") (name "/nDAT01") (class "Default")
      (node (ref "R1") (pin "2") (pinfunction "2_2") (pintype "passive"))
      (node (ref "U5") (pin "43") (pinfunction "PA10_43") (pintype "passive"))
    )
    (net (code "26") (name "/nDAT02") (class "Default")
      (node (ref "U2") (pin "3") (pinfunction "2A_3") (pintype "passive"))
      (node (ref "U5") (pin "41") (pinfunction "PA8_41") (pintype "passive"))
    )
    (net (code "27") (name "/nDAT03") (class "Default")
      (node (ref "U3") (pin "3") (pinfunction "2A_3") (pintype "passive"))
      (node (ref "U5") (pin "23") (pinfunction "PA7_23") (pintype "passive"))
    )
    (net (code "28") (name "/nDAT04") (class "Default")
      (node (ref "U3") (pin "2") (pinfunction "1A_2") (pintype "passive"))
      (node (ref "U5") (pin "40") (pinfunction "PC9_40") (pintype "passive"))
    )
    (net (code "29") (name "/nDAT05") (class "Default")
      (node (ref "R1") (pin "1") (pinfunction "1_1") (pintype "passive"))
      (node (ref "U5") (pin "39") (pinfunction "PC8_39") (pintype "passive"))
    )
    (net (code "30") (name "/nDAT06") (class "Default")
      (node (ref "U5") (pin "35") (pinfunction "PB14_35") (pintype "passive"))
      (node (ref "U7") (pin "3") (pinfunction "2A_3") (pintype "passive"))
    )
    (net (code "31") (name "/nDAT07") (class "Default")
      (node (ref "U5") (pin "22") (pinfunction "PA6_22") (pintype "passive"))
      (node (ref "U8") (pin "3") (pinfunction "2A_3") (pintype "passive"))
    )
    (net (code "32") (name "/nDAT08") (class "Default")
      (node (ref "R26") (pin "2") (pinfunction "2_2") (pintype "passive"))
      (node (ref "R28") (pin "2") (pinfunction "2_2") (pintype "passive"))
      (node (ref "R33") (pin "1") (pinfunction "1_1") (pintype "passive"))
      (node (ref "U9") (pin "3") (pinfunction "2A_3") (pintype "passive"))
    )
    (net (code "33") (name "/nDAT09") (class "Default")
      (node (ref "U5") (pin "27") (pinfunction "PB1_27") (pintype "passive"))
      (node (ref "U5") (pin "33") (pinfunction "PB12_33") (pintype "passive"))
    )
    (net (code "34") (name "/nDAT10") (class "Default")
      (node (ref "U4") (pin "2") (pinfunction "1A_2") (pintype "passive"))
      (node (ref "U5") (pin "28") (pinfunction "PB2_28") (pintype "passive"))
    )
    (net (code "35") (name "/nDAT11") (class "Default")
      (node (ref "R14") (pin "2") (pinfunction "2_2") (pintype "passive"))
      (node (ref "R25") (pin "2") (pinfunction "2_2") (pintype "passive"))
      (node (ref "R27") (pin "2") (pinfunction "2_2") (pintype "passive"))
      (node (ref "U2") (pin "2") (pinfunction "1A_2") (pintype "passive"))
    )
    (net (code "36") (name "/nDAT12") (class "Default")
      (node (ref "U4") (pin "3") (pinfunction "2A_3") (pintype "passive"))
      (node (ref "U5") (pin "25") (pinfunction "PC5_25") (pintype "passive"))
    )
    (net (code "37") (name "/nPWR") (class "Default")
      (node (ref "Q2") (pin "1") (pinfunction "G_1") (pintype "passive"))
      (node (ref "R17") (pin "1") (pinfunction "1_1") (pintype "passive"))
      (node (ref "U5") (pin "59") (pinfunction "PB7_59") (pintype "passive"))
    )
    (net (code "38") (name "/nSRST") (class "Default")
      (node (ref "Q1") (pin "1") (pinfunction "B_1") (pintype "passive"))
      (node (ref "U5") (pin "61") (pinfunction "PB8_61") (pintype "passive"))
    )
    (net (code "39") (name "/pADC1") (class "Default")
      (node (ref "C7") (pin "1") (pinfunction "1_1") (pintype "passive"))
      (node (ref "R30") (pin "1") (pinfunction "1_1") (pintype "passive"))
      (node (ref "R34") (pin "2") (pinfunction "2_2") (pintype "passive"))
      (node (ref "U5") (pin "8") (pinfunction "PC0_8") (pintype "passive"))
    )
    (net (code "40") (name "/pADC2") (class "Default")
      (node (ref "C8") (pin "1") (pinfunction "1_1") (pintype "passive"))
      (node (ref "R23") (pin "1") (pinfunction "1_1") (pintype "passive"))
      (node (ref "R24") (pin "1") (pinfunction "1_1") (pintype "passive"))
      (node (ref "R31") (pin "1") (pinfunction "1_1") (pintype "passive"))
      (node (ref "R35") (pin "2") (pinfunction "2_2") (pintype "passive"))
    )
    (net (code "41") (name "/pADC4") (class "Default")
      (node (ref "C9") (pin "1") (pinfunction "1_1") (pintype "passive"))
      (node (ref "R32") (pin "1") (pinfunction "1_1") (pintype "passive"))
      (node (ref "R36") (pin "2") (pinfunction "2_2") (pintype "passive"))
      (node (ref "U5") (pin "14") (pinfunction "PA0-WKUP_14") (pintype "passive"))
    )
    (net (code "42") (name "/pLED1") (class "Default")
      (node (ref "D1") (pin "C") (pinfunction "C_C") (pintype "passive"))
      (node (ref "U5") (pin "30") (pinfunction "PB11_30") (pintype "passive"))
    )
    (net (code "43") (name "/pLED2") (class "Default")
      (node (ref "D2") (pin "C") (pinfunction "C_C") (pintype "passive"))
      (node (ref "U5") (pin "29") (pinfunction "PB10_29") (pintype "passive"))
    )
    (net (code "44") (name "/tNRST") (class "Default")
      (node (ref "P1") (pin "10") (pinfunction "10_10") (pintype "passive"))
      (node (ref "R16") (pin "2") (pinfunction "2_2") (pintype "passive"))
      (node (ref "R2") (pin "1") (pinfunction "1_1") (pintype "passive"))
      (node (ref "R5") (pin "2") (pinfunction "2_2") (pintype "passive"))
      (node (ref "R51") (pin "2") (pinfunction "2_2") (pintype "passive"))
    )
    (net (code "45") (name "/tRXD") (class "Default")
      (node (ref "P1") (pin "7") (pinfunction "7_7") (pintype "passive"))
      (node (ref "R15") (pin "2") (pinfunction "2_2") (pintype "passive"))
      (node (ref "R46") (pin "1") (pinfunction "1_1") (pintype "passive"))
      (node (ref "R53") (pin "2") (pinfunction "2_2") (pintype "passive"))
    )
    (net (code "46") (name "/tTCK") (class "Default")
      (node (ref "P1") (pin "4") (pinfunction "4_4") (pintype "passive"))
      (node (ref "R10") (pin "2") (pinfunction "2_2") (pintype "passive"))
      (node (ref "R37") (pin "2") (pinfunction "2_2") (pintype "passive"))
      (node (ref "R48") (pin "2") (pinfunction "2_2") (pintype "passive"))
    )
    (net (code "47") (name "/tTDI") (class "Default")
      (node (ref "P1") (pin "8") (pinfunction "8_8") (pintype "passive"))
      (node (ref "R20") (pin "2") (pinfunction "2_2") (pintype "passive"))
      (node (ref "R50") (pin "2") (pinfunction "2_2") (pintype "passive"))
      (node (ref "R7") (pin "2") (pinfunction "2_2") (pintype "passive"))
    )
    (net (code "48") (name "/tTDO") (class "Default")
      (node (ref "P1") (pin "6") (pinfunction "6_6") (pintype "passive"))
      (node (ref "R49") (pin "2") (pinfunction "2_2") (pintype "passive"))
      (node (ref "R6") (pin "2") (pinfunction "2_2") (pintype "passive"))
    )
    (net (code "49") (name "/tTMS") (class "Default")
      (node (ref "P1") (pin "2") (pinfunction "2_2") (pintype "passive"))
      (node (ref "R11") (pin "2") (pinfunction "2_2") (pintype "passive"))
      (node (ref "R29") (pin "2") (pinfunction "2_2") (pintype "passive"))
      (node (ref "R47") (pin "2") (pinfunction "2_2") (pintype "passive"))
    )
    (net (code "50") (name "/tVREF") (class "Default")
      (node (ref "C26") (pin "1") (pinfunction "1_1") (pintype "passive"))
      (node (ref "P1") (pin "1") (pinfunction "1_1") (pintype "passive"))
      (node (ref "R38") (pin "2") (pinfunction "2_2") (pintype "passive"))
      (node (ref "R43") (pin "2") (pinfunction "2_2") (pintype "passive"))
      (node (ref "R52") (pin "2") (pinfunction "2_2") (pintype "passive"))
    )
    (net (code "51") (name "3V3_CORE") (class "Default")
      (node (ref "C11") (pin "1") (pinfunction "1_1") (pintype "passive"))
      (node (ref "C12") (pin "1") (pinfunction "1_1") (pintype "passive"))
      (node (ref "C16") (pin "1") (pinfunction "1_1") (pintype "passive"))
      (node (ref "C17") (pin "1") (pinfunction "1_1") (pintype "passive"))
      (node (ref "C20") (pin "1") (pinfunction "1_1") (pintype "passive"))
      (node (ref "C21") (pin "1") (pinfunction "1_1") (pintype "passive"))
      (node (ref "C22") (pin "1") (pinfunction "1_1") (pintype "passive"))
      (node (ref "C3") (pin "1") (pinfunction "1_1") (pintype "passive"))
      (node (ref "P2") (pin "1") (pinfunction "1_1") (pintype "passive"))
      (node (ref "Q3") (pin "1") (pinfunction "S1_1") (pintype "passive"))
      (node (ref "R12") (pin "1") (pinfunction "1_1") (pintype "passive"))
      (node (ref "R18") (pin "1") (pinfunction "1_1") (pintype "passive"))
      (node (ref "R19") (pin "1") (pinfunction "1_1") (pintype "passive"))
      (node (ref "R21") (pin "2") (pinfunction "2_2") (pintype "passive"))
      (node (ref "R22") (pin "1") (pinfunction "1_1") (pintype "passive"))
      (node (ref "R3") (pin "2") (pinfunction "2_2") (pintype "passive"))
      (node (ref "R39") (pin "2") (pinfunction "2_2") (pintype "passive"))
      (node (ref "R4") (pin "2") (pinfunction "2_2") (pintype "passive"))
      (node (ref "U10") (pin "5") (pinfunction "IN_5") (pintype "passive"))
      (node (ref "U2") (pin "1") (pinfunction "VCC(A)_1") (pintype "passive"))
      (node (ref "U3") (pin "1") (pinfunction "VCC(A)_1") (pintype "passive"))
      (node (ref "U4") (pin "1") (pinfunction "VCC(A)_1") (pintype "passive"))
      (node (ref "U5") (pin "12") (pinfunction "VSSA_12") (pintype "passive"))
      (node (ref "U5") (pin "19") (pinfunction "VDD_1_19") (pintype "passive"))
      (node (ref "U5") (pin "48") (pinfunction "VDD_3_48") (pintype "passive"))
      (node (ref "U5") (pin "64") (pinfunction "VDD_4_64") (pintype "passive"))
      (node (ref "U6") (pin "2") (pinfunction "VOUT_2") (pintype "power_in"))
      (node (ref "U7") (pin "1") (pinfunction "VCC(A)_1") (pintype "passive"))
      (node (ref "U8") (pin "1") (pinfunction "VCC(A)_1") (pintype "passive"))
      (node (ref "U9") (pin "1") (pinfunction "VCC(A)_1") (pintype "passive"))
    )
    (net (code "52") (name "GND") (class "Default")
      (node (ref "C1") (pin "2") (pinfunction "2_2") (pintype "passive"))
      (node (ref "C10") (pin "2") (pinfunction "2_2") (pintype "passive"))
      (node (ref "C11") (pin "2") (pinfunction "2_2") (pintype "passive"))
      (node (ref "C12") (pin "2") (pinfunction "2_2") (pintype "passive"))
      (node (ref "C16") (pin "2") (pinfunction "2_2") (pintype "passive"))
      (node (ref "C17") (pin "2") (pinfunction "2_2") (pintype "passive"))
      (node (ref "C18") (pin "2") (pinfunction "2_2") (pintype "passive"))
      (node (ref "C19") (pin "2") (pinfunction "2_2") (pintype "passive"))
      (node (ref "C2") (pin "2") (pinfunction "2_2") (pintype "passive"))
      (node (ref "C20") (pin "2") (pinfunction "2_2") (pintype "passive"))
      (node (ref "C23") (pin "2") (pinfunction "2_2") (pintype "passive"))
      (node (ref "C24") (pin "2") (pinfunction "2_2") (pintype "passive"))
      (node (ref "C25") (pin "2") (pinfunction "2_2") (pintype "passive"))
      (node (ref "C26") (pin "2") (pinfunction "2_2") (pintype "passive"))
      (node (ref "C27") (pin "2") (pinfunction "2_2") (pintype "passive"))
      (node (ref "C3") (pin "2") (pinfunction "2_2") (pintype "passive"))
      (node (ref "C4") (pin "2") (pinfunction "2_2") (pintype "passive"))
      (node (ref "C5") (pin "1") (pinfunction "1_1") (pintype "passive"))
      (node (ref "C6") (pin "2") (pinfunction "2_2") (pintype "passive"))
      (node (ref "C7") (pin "2") (pinfunction "2_2") (pintype "passive"))
      (node (ref "C8") (pin "2") (pinfunction "2_2") (pintype "passive"))
      (node (ref "C9") (pin "2") (pinfunction "2_2") (pintype "passive"))
      (node (ref "D3") (pin "C") (pinfunction "C_C") (pintype "passive"))
      (node (ref "D4") (pin "C") (pinfunction "C_C") (pintype "passive"))
      (node (ref "J1") (pin "0") (pinfunction "0_0") (pintype "passive"))
      (node (ref "J1") (pin "A1") (pinfunction "GND_A1") (pintype "passive"))
      (node (ref "J1") (pin "A12") (pinfunction "GND_A12") (pintype "passive"))
      (node (ref "J1") (pin "B1") (pinfunction "GND_B1") (pintype "passive"))
      (node (ref "J1") (pin "B12") (pinfunction "GND_B12") (pintype "passive"))
      (node (ref "P1") (pin "3") (pinfunction "3_3") (pintype "passive"))
      (node (ref "P1") (pin "5") (pinfunction "5_5") (pintype "passive"))
      (node (ref "P2") (pin "4") (pinfunction "4_4") (pintype "passive"))
      (node (ref "Q1") (pin "2") (pinfunction "E_2") (pintype "power_in"))
      (node (ref "Q3") (pin "4") (pinfunction "S2_4") (pintype "passive"))
      (node (ref "Q5") (pin "2") (pinfunction "E_2") (pintype "power_in"))
      (node (ref "R13") (pin "1") (pinfunction "1_1") (pintype "passive"))
      (node (ref "R34") (pin "1") (pinfunction "1_1") (pintype "passive"))
      (node (ref "R35") (pin "1") (pinfunction "1_1") (pintype "passive"))
      (node (ref "R36") (pin "1") (pinfunction "1_1") (pintype "passive"))
      (node (ref "R45") (pin "1") (pinfunction "1_1") (pintype "passive"))
      (node (ref "R47") (pin "1") (pinfunction "1_1") (pintype "passive"))
      (node (ref "R48") (pin "1") (pinfunction "1_1") (pintype "passive"))
      (node (ref "R49") (pin "1") (pinfunction "1_1") (pintype "passive"))
      (node (ref "R50") (pin "1") (pinfunction "1_1") (pintype "passive"))
      (node (ref "R51") (pin "1") (pinfunction "1_1") (pintype "passive"))
      (node (ref "R52") (pin "1") (pinfunction "1_1") (pintype "passive"))
      (node (ref "R53") (pin "1") (pinfunction "1_1") (pintype "passive"))
      (node (ref "R8") (pin "1") (pinfunction "1_1") (pintype "passive"))
      (node (ref "R9") (pin "1") (pinfunction "1_1") (pintype "passive"))
      (node (ref "U1") (pin "2") (pinfunction "2_2") (pintype "passive"))
      (node (ref "U10") (pin "2") (pinfunction "GND_2") (pintype "passive"))
      (node (ref "U11") (pin "2") (pinfunction "V-_2") (pintype "passive"))
      (node (ref "U2") (pin "4") (pinfunction "GND_4") (pintype "passive"))
      (node (ref "U2") (pin "5") (pinfunction "DIR_5") (pintype "passive"))
      (node (ref "U3") (pin "4") (pinfunction "GND_4") (pintype "passive"))
      (node (ref "U3") (pin "5") (pinfunction "DIR_5") (pintype "passive"))
      (node (ref "U4") (pin "4") (pinfunction "GND_4") (pintype "passive"))
      (node (ref "U4") (pin "5") (pinfunction "DIR_5") (pintype "passive"))
      (node (ref "U5") (pin "13") (pinfunction "VDDA_13") (pintype "passive"))
      (node (ref "U5") (pin "18") (pinfunction "VSS_1_18") (pintype "passive"))
      (node (ref "U5") (pin "63") (pinfunction "VSS_2_63") (pintype "passive"))
      (node (ref "U6") (pin "1") (pinfunction "VSS_1") (pintype "passive"))
      (node (ref "U7") (pin "2") (pinfunction "1A_2") (pintype "passive"))
      (node (ref "U7") (pin "4") (pinfunction "GND_4") (pintype "passive"))
      (node (ref "U7") (pin "7") (pinfunction "1B_7") (pintype "passive"))
      (node (ref "U8") (pin "2") (pinfunction "1A_2") (pintype "passive"))
      (node (ref "U8") (pin "4") (pinfunction "GND_4") (pintype "passive"))
      (node (ref "U8") (pin "7") (pinfunction "1B_7") (pintype "passive"))
      (node (ref "U9") (pin "2") (pinfunction "1A_2") (pintype "passive"))
      (node (ref "U9") (pin "4") (pinfunction "GND_4") (pintype "passive"))
      (node (ref "U9") (pin "7") (pinfunction "1B_7") (pintype "passive"))
      (node (ref "X1") (pin "2") (pinfunction "GND_2") (pintype "power_in"))
      (node (ref "X1") (pin "4") (pinfunction "GND_4") (pintype "power_in"))
    )
    (net (code "53") (name "Net-(C21-Pad2)") (class "Default")
      (node (ref "C21") (pin "2") (pinfunction "2_2") (pintype "passive"))
      (node (ref "K1") (pin "1") (pinfunction "1_1") (pintype "passive"))
      (node (ref "R42") (pin "1") (pinfunction "1_1") (pintype "passive"))
    )
    (net (code "54") (name "Net-(D1-PadA)") (class "Default")
      (node (ref "D1") (pin "A") (pinfunction "A_A") (pintype "passive"))
      (node (ref "R18") (pin "2") (pinfunction "2_2") (pintype "passive"))
    )
    (net (code "55") (name "Net-(D2-PadA)") (class "Default")
      (node (ref "D2") (pin "A") (pinfunction "A_A") (pintype "passive"))
      (node (ref "R19") (pin "2") (pinfunction "2_2") (pintype "passive"))
    )
    (net (code "56") (name "Net-(D3-PadA)") (class "Default")
      (node (ref "D3") (pin "A") (pinfunction "A_A") (pintype "passive"))
      (node (ref "R22") (pin "2") (pinfunction "2_2") (pintype "passive"))
    )
    (net (code "57") (name "Net-(D4-PadA)") (class "Default")
      (node (ref "D4") (pin "A") (pinfunction "A_A") (pintype "passive"))
      (node (ref "R41") (pin "1") (pinfunction "1_1") (pintype "passive"))
    )
    (net (code "58") (name "Net-(J1-CC1)") (class "Default")
      (node (ref "J1") (pin "A5") (pinfunction "CC1_A5") (pintype "passive"))
      (node (ref "R9") (pin "2") (pinfunction "2_2") (pintype "passive"))
    )
    (net (code "59") (name "Net-(J1-CC2)") (class "Default")
      (node (ref "J1") (pin "B5") (pinfunction "CC2_B5") (pintype "passive"))
      (node (ref "R8") (pin "2") (pinfunction "2_2") (pintype "passive"))
    )
    (net (code "60") (name "Net-(Q1-C)") (class "Default")
      (node (ref "Q1") (pin "3") (pinfunction "C_3") (pintype "power_in"))
      (node (ref "R5") (pin "1") (pinfunction "1_1") (pintype "passive"))
    )
    (net (code "61") (name "Net-(Q3-D1)") (class "Default")
      (node (ref "C24") (pin "1") (pinfunction "1_1") (pintype "passive"))
      (node (ref "Q3") (pin "6") (pinfunction "D1_6") (pintype "passive"))
      (node (ref "R40") (pin "2") (pinfunction "2_2") (pintype "passive"))
      (node (ref "R41") (pin "2") (pinfunction "2_2") (pintype "passive"))
      (node (ref "U10") (pin "4") (pinfunction "~{EN}_4") (pintype "passive"))
    )
    (net (code "62") (name "Net-(Q3-D2)") (class "Default")
      (node (ref "C22") (pin "2") (pinfunction "2_2") (pintype "passive"))
      (node (ref "Q3") (pin "2") (pinfunction "G1_2") (pintype "passive"))
      (node (ref "Q3") (pin "3") (pinfunction "D2_3") (pintype "passive"))
      (node (ref "R39") (pin "1") (pinfunction "1_1") (pintype "passive"))
      (node (ref "R42") (pin "2") (pinfunction "2_2") (pintype "passive"))
    )
    (net (code "63") (name "Net-(Q3-G2)") (class "Default")
      (node (ref "K1") (pin "2") (pinfunction "2_2") (pintype "passive"))
      (node (ref "Q3") (pin "5") (pinfunction "G2_5") (pintype "passive"))
      (node (ref "R40") (pin "1") (pinfunction "1_1") (pintype "passive"))
      (node (ref "R45") (pin "2") (pinfunction "2_2") (pintype "passive"))
    )
    (net (code "64") (name "Net-(Q4-D)") (class "Default")
      (node (ref "Q4") (pin "3") (pinfunction "D_3") (pintype "passive"))
      (node (ref "R54") (pin "2") (pinfunction "2_2") (pintype "passive"))
      (node (ref "U11") (pin "4") (pinfunction "IN-_4") (pintype "passive"))
    )
    (net (code "65") (name "Net-(Q4-G)") (class "Default")
      (node (ref "Q4") (pin "1") (pinfunction "G_1") (pintype "passive"))
      (node (ref "Q5") (pin "3") (pinfunction "C_3") (pintype "power_in"))
      (node (ref "R44") (pin "1") (pinfunction "1_1") (pintype "passive"))
    )
    (net (code "66") (name "Net-(Q5-B)") (class "Default")
      (node (ref "Q5") (pin "1") (pinfunction "B_1") (pintype "passive"))
      (node (ref "U11") (pin "1") (pinfunction "OUT_1") (pintype "passive"))
    )
    (net (code "67") (name "Net-(U2-1B)") (class "Default")
      (node (ref "R6") (pin "1") (pinfunction "1_1") (pintype "passive"))
      (node (ref "U2") (pin "7") (pinfunction "1B_7") (pintype "passive"))
    )
    (net (code "68") (name "Net-(U2-2B)") (class "Default")
      (node (ref "R7") (pin "1") (pinfunction "1_1") (pintype "passive"))
      (node (ref "U2") (pin "6") (pinfunction "2B_6") (pintype "passive"))
    )
    (net (code "69") (name "Net-(U3-1B)") (class "Default")
      (node (ref "R10") (pin "1") (pinfunction "1_1") (pintype "passive"))
      (node (ref "U3") (pin "7") (pinfunction "1B_7") (pintype "passive"))
    )
    (net (code "70") (name "Net-(U3-2B)") (class "Default")
      (node (ref "R11") (pin "1") (pinfunction "1_1") (pintype "passive"))
      (node (ref "U3") (pin "6") (pinfunction "2B_6") (pintype "passive"))
    )
    (net (code "71") (name "Net-(U4-1B)") (class "Default")
      (node (ref "R15") (pin "1") (pinfunction "1_1") (pintype "passive"))
      (node (ref "U4") (pin "7") (pinfunction "1B_7") (pintype "passive"))
    )
    (net (code "72") (name "Net-(U4-2B)") (class "Default")
      (node (ref "R16") (pin "1") (pinfunction "1_1") (pintype "passive"))
      (node (ref "U4") (pin "6") (pinfunction "2B_6") (pintype "passive"))
    )
    (net (code "73") (name "Net-(U5-VCAP_1)") (class "Default")
      (node (ref "C6") (pin "1") (pinfunction "1_1") (pintype "passive"))
      (node (ref "U5") (pin "31") (pinfunction "VCAP_1_31") (pintype "passive"))
    )
    (net (code "74") (name "Net-(U5-VCAP_2)") (class "Default")
      (node (ref "C4") (pin "1") (pinfunction "1_1") (pintype "passive"))
      (node (ref "U5") (pin "47") (pinfunction "VCAP_2_47") (pintype "passive"))
    )
    (net (code "75") (name "Net-(U7-2B)") (class "Default")
      (node (ref "R20") (pin "1") (pinfunction "1_1") (pintype "passive"))
      (node (ref "U7") (pin "6") (pinfunction "2B_6") (pintype "passive"))
    )
    (net (code "76") (name "Net-(U8-2B)") (class "Default")
      (node (ref "R29") (pin "1") (pinfunction "1_1") (pintype "passive"))
      (node (ref "U8") (pin "6") (pinfunction "2B_6") (pintype "passive"))
    )
    (net (code "77") (name "Net-(U9-2B)") (class "Default")
      (node (ref "R37") (pin "1") (pinfunction "1_1") (pintype "passive"))
      (node (ref "U9") (pin "6") (pinfunction "2B_6") (pintype "passive"))
    )
    (net (code "78") (name "Net-(U10-OUT)") (class "Default")
      (node (ref "C18") (pin "1") (pinfunction "1_1") (pintype "passive"))
      (node (ref "R38") (pin "1") (pinfunction "1_1") (pintype "passive"))
      (node (ref "U10") (pin "1") (pinfunction "OUT_1") (pintype "passive"))
    )
    (net (code "79") (name "VCC_TGT") (class "Default")
      (node (ref "C27") (pin "1") (pinfunction "1_1") (pintype "passive"))
      (node (ref "R2") (pin "2") (pinfunction "2_2") (pintype "passive"))
      (node (ref "R30") (pin "2") (pinfunction "2_2") (pintype "passive"))
      (node (ref "R46") (pin "2") (pinfunction "2_2") (pintype "passive"))
      (node (ref "R54") (pin "1") (pinfunction "1_1") (pintype "passive"))
      (node (ref "U2") (pin "8") (pinfunction "VCC(B)_8") (pintype "passive"))
      (node (ref "U3") (pin "8") (pinfunction "VCC(B)_8") (pintype "passive"))
      (node (ref "U4") (pin "8") (pinfunction "VCC(B)_8") (pintype "passive"))
      (node (ref "U7") (pin "8") (pinfunction "VCC(B)_8") (pintype "passive"))
      (node (ref "U8") (pin "8") (pinfunction "VCC(B)_8") (pintype "passive"))
      (node (ref "U9") (pin "8") (pinfunction "VCC(B)_8") (pintype "passive"))
    )
    (net (code "80") (name "VOUT") (class "Default")
      (node (ref "P1") (pin "9") (pinfunction "9_9") (pintype "passive"))
      (node (ref "Q2") (pin "3") (pinfunction "D_3") (pintype "passive"))
      (node (ref "R32") (pin "2") (pinfunction "2_2") (pintype "passive"))
    )
    (net (code "81") (name "unconnected-(J1-SBU1-PadA8)") (class "Default")
      (node (ref "J1") (pin "A8") (pinfunction "SBU1_A8") (pintype "passive+no_connect"))
    )
    (net (code "82") (name "unconnected-(J1-SBU2-PadB8)") (class "Default")
      (node (ref "J1") (pin "B8") (pinfunction "SBU2_B8") (pintype "passive+no_connect"))
    )
    (net (code "83") (name "unconnected-(K1-Pad3)") (class "Default")
      (node (ref "K1") (pin "3") (pinfunction "3_3") (pintype "passive+no_connect"))
    )
    (net (code "84") (name "unconnected-(K1-Pad4)") (class "Default")
      (node (ref "K1") (pin "4") (pinfunction "4_4") (pintype "passive+no_connect"))
    )
    (net (code "85") (name "unconnected-(U5-PA1-Pad15)") (class "Default")
      (node (ref "U5") (pin "15") (pinfunction "PA1_15") (pintype "passive+no_connect"))
    )
    (net (code "86") (name "unconnected-(U5-PA4-Pad20)") (class "Default")
      (node (ref "U5") (pin "20") (pinfunction "PA4_20") (pintype "passive+no_connect"))
    )
    (net (code "87") (name "unconnected-(U5-PA9-Pad42)") (class "Default")
      (node (ref "U5") (pin "42") (pinfunction "PA9_42") (pintype "passive+no_connect"))
    )
    (net (code "88") (name "unconnected-(U5-PA15-Pad50)") (class "Default")
      (node (ref "U5") (pin "50") (pinfunction "PA15_50") (pintype "passive+no_connect"))
    )
    (net (code "89") (name "unconnected-(U5-PB0-Pad26)") (class "Default")
      (node (ref "U5") (pin "26") (pinfunction "PB0_26") (pintype "passive+no_connect"))
    )
    (net (code "90") (name "unconnected-(U5-PB3-Pad55)") (class "Default")
      (node (ref "U5") (pin "55") (pinfunction "PB3_55") (pintype "passive+no_connect"))
    )
    (net (code "91") (name "unconnected-(U5-PB4-Pad56)") (class "Default")
      (node (ref "U5") (pin "56") (pinfunction "PB4_56") (pintype "passive+no_connect"))
    )
    (net (code "92") (name "unconnected-(U5-PB5-Pad57)") (class "Default")
      (node (ref "U5") (pin "57") (pinfunction "PB5_57") (pintype "passive+no_connect"))
    )
    (net (code "93") (name "unconnected-(U5-PB6-Pad58)") (class "Default")
      (node (ref "U5") (pin "58") (pinfunction "PB6_58") (pintype "passive+no_connect"))
    )
    (net (code "94") (name "unconnected-(U5-PB9-Pad62)") (class "Default")
      (node (ref "U5") (pin "62") (pinfunction "PB9_62") (pintype "passive+no_connect"))
    )
    (net (code "95") (name "unconnected-(U5-PC4-Pad24)") (class "Default")
      (node (ref "U5") (pin "24") (pinfunction "PC4_24") (pintype "passive+no_connect"))
    )
    (net (code "96") (name "unconnected-(U5-PC10-Pad51)") (class "Default")
      (node (ref "U5") (pin "51") (pinfunction "PC10_51") (pintype "passive+no_connect"))
    )
    (net (code "97") (name "unconnected-(U5-PC11-Pad52)") (class "Default")
      (node (ref "U5") (pin "52") (pinfunction "PC11_52") (pintype "passive+no_connect"))
    )
    (net (code "98") (name "unconnected-(U5-PC13-RTC_AF1-Pad2)") (class "Default")
      (node (ref "U5") (pin "2") (pinfunction "PC13-RTC_AF1_2") (pintype "passive+no_connect"))
    )
    (net (code "99") (name "unconnected-(U5-PC14-OSC32_IN-Pad3)") (class "Default")
      (node (ref "U5") (pin "3") (pinfunction "PC14-OSC32_IN_3") (pintype "passive+no_connect"))
    )
    (net (code "100") (name "unconnected-(U5-PC15-OSC32_OUT-Pad4)") (class "Default")
      (node (ref "U5") (pin "4") (pinfunction "PC15-OSC32_OUT_4") (pintype "passive+no_connect"))
    )
    (net (code "101") (name "unconnected-(U5-PD2-Pad54)") (class "Default")
      (node (ref "U5") (pin "54") (pinfunction "PD2_54") (pintype "passive+no_connect"))
    )
    (net (code "102") (name "unconnected-(U5-VBAT-Pad1)") (class "Default")
      (node (ref "U5") (pin "1") (pinfunction "VBAT_1") (pintype "passive"))
    )
    (net (code "103") (name "unconnected-(U5-VDD_2-Pad32)") (class "Default")
      (node (ref "U5") (pin "32") (pinfunction "VDD_2_32") (pintype "passive"))
    )
    (net (code "104") (name "unconnected-(U10-~{OC}-Pad3)") (class "Default")
      (node (ref "U10") (pin "3") (pinfunction "~{OC}_3") (pintype "passive+no_connect"))
    )
  )
)
